# MCU.net
KiCad netlist of a schematic drawn in Altium Designer
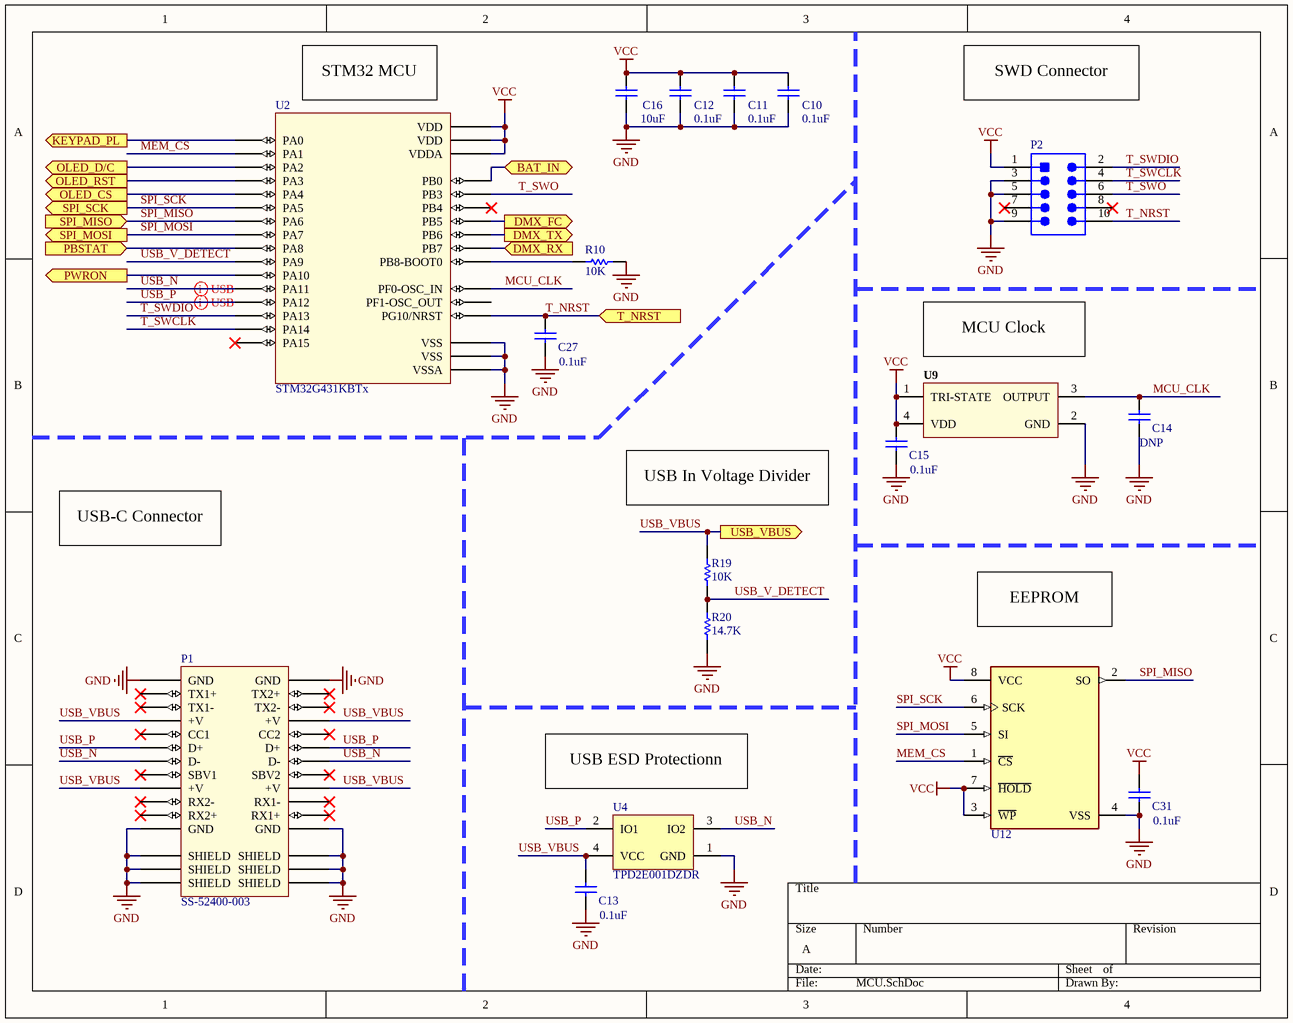
[diagram p0: MCU.SchDoc]

(export (version "E")
  (design (tool "Eeschema 10.0.6"))
  (components
    (comp (ref "C10")
      (value "0.1uF")
      (footprint "CAPC0603(1608)100_L")
      (description "CAP 27pF 16V ±0.5pF 0603 (1608 Metric) Thickness 1mm SMD")
      (fields (field (name "TOLERANCE") "Â±0.5pF"))
      (libsource (lib "Altium Content Vault") (part "CMP-1035-00873-1"))
    )
    (comp (ref "C11")
      (value "0.1uF")
      (footprint "CAPC0603(1608)100_L")
      (description "CAP 27pF 16V ±0.5pF 0603 (1608 Metric) Thickness 1mm SMD")
      (fields (field (name "TOLERANCE") "Â±0.5pF"))
      (libsource (lib "Altium Content Vault") (part "CMP-1035-00873-1"))
    )
    (comp (ref "C12")
      (value "0.1uF")
      (footprint "CAPC0603(1608)100_L")
      (description "CAP 27pF 16V ±0.5pF 0603 (1608 Metric) Thickness 1mm SMD")
      (fields (field (name "TOLERANCE") "Â±0.5pF"))
      (libsource (lib "Altium Content Vault") (part "CMP-1035-00873-1"))
    )
    (comp (ref "C13")
      (value "0.1uF")
      (footprint "CAPC0603(1608)100_L")
      (description "CAP 27pF 16V ±0.5pF 0603 (1608 Metric) Thickness 1mm SMD")
      (fields (field (name "TOLERANCE") "Â±0.5pF"))
      (libsource (lib "Altium Content Vault") (part "CMP-1035-00873-1"))
    )
    (comp (ref "C14")
      (value "DNP")
      (footprint "CAPC0603(1608)100_L")
      (description "CAP 27pF 16V ±0.5pF 0603 (1608 Metric) Thickness 1mm SMD")
      (fields (field (name "TOLERANCE") "Â±0.5pF"))
      (libsource (lib "Altium Content Vault") (part "CMP-1035-00873-1"))
    )
    (comp (ref "C15")
      (value "0.1uF")
      (footprint "CAPC0603(1608)100_L")
      (description "CAP 27pF 16V ±0.5pF 0603 (1608 Metric) Thickness 1mm SMD")
      (fields (field (name "TOLERANCE") "Â±0.5pF"))
      (libsource (lib "Altium Content Vault") (part "CMP-1035-00873-1"))
    )
    (comp (ref "C16")
      (value "10uF")
      (footprint "CAPC0603(1608)100_L")
      (description "CAP 27pF 16V ±0.5pF 0603 (1608 Metric) Thickness 1mm SMD")
      (fields (field (name "TOLERANCE") "Â±0.5pF"))
      (libsource (lib "Altium Content Vault") (part "CMP-1035-00873-1"))
    )
    (comp (ref "C27")
      (value "0.1uF")
      (footprint "CAPC0603(1608)100_L")
      (description "CAP 27pF 16V ±0.5pF 0603 (1608 Metric) Thickness 1mm SMD")
      (fields (field (name "TOLERANCE") "Â±0.5pF"))
      (libsource (lib "Altium Content Vault") (part "CMP-1035-00873-1"))
    )
    (comp (ref "C31")
      (value "0.1uF")
      (footprint "CAPC0603(1608)100_L")
      (description "CAP 27pF 16V ±0.5pF 0603 (1608 Metric) Thickness 1mm SMD")
      (fields (field (name "TOLERANCE") "Â±0.5pF"))
      (libsource (lib "Altium Content Vault") (part "CMP-1035-00873-1"))
    )
    (comp (ref "P1")
      (value "SS-52400-003")
      (footprint "SS-52400-00X")
      (libsource (lib "Belfuse") (part "SS-52400-003"))
    )
    (comp (ref "P2")
      (value "FTSH-105-01-F-DV-K")
      (footprint "SMTC-FTSH-105-01-L-DV-K_V")
      (description "Male Header, Pitch 1.27 mm, 2 x 5 Position, Height 6.12 mm, RoHS, Tube")
      (fields (field (name "MANUFACTURER") "Samtec"))
      (libsource (lib "Altium Content Vault") (part "CMP-2000-05352-1"))
    )
    (comp (ref "R10")
      (value "10K")
      (footprint "RESC0603(1608)_N")
      (description "Jumper 0603 (1608 Metric)")
      (fields (field (name "POWER") "None"))
      (libsource (lib "Altium Content Vault") (part "CMP-1012-00001-1"))
    )
    (comp (ref "R19")
      (value "10K")
      (footprint "RESC0603(1608)_N")
      (description "Jumper 0603 (1608 Metric)")
      (fields (field (name "POWER") "None"))
      (libsource (lib "Altium Content Vault") (part "CMP-1012-00001-1"))
    )
    (comp (ref "R20")
      (value "14.7K")
      (footprint "RESC0603(1608)_N")
      (description "Jumper 0603 (1608 Metric)")
      (fields (field (name "POWER") "None"))
      (libsource (lib "Altium Content Vault") (part "CMP-1012-00001-1"))
    )
    (comp (ref "U2")
      (value "STM32G431KBTx")
      (footprint "LQFP32")
      (libsource (lib "STMicroelectronics") (part "STM32G431KBTx"))
    )
    (comp (ref "U4")
      (value "TPD2E001DZDR")
      (footprint "DZD0004A_N")
      (fields (field (name "MANUFACTURER") "Texas Instruments"))
      (libsource (lib "Altium Content Vault") (part "TI-TPD2E001-SOP_DZD-4"))
    )
    (comp (ref "U9")
      (value "XLH536024.000000I")
      (footprint "ECS-396X_V")
      (description "Clock Oscillator, 3.3 V, 25 MHz, -55 to 125 degC, 4-Pin SMD, RoHS, Tape and Reel")
      (fields (field (name "MANUFACTURER") "ECS"))
      (libsource (lib "Altium Content Vault") (part "CMP-2000-06192-1"))
    )
    (comp (ref "U12")
      (value "CAT25640VI-GT3")
      (footprint "FP-CAT25256VI-GT3-IPC_B")
      (description "IC EEPROM 256K SPI 20MHZ 8SOIC")
      (fields
        (field (name "MANUFACTURER") "ON Semiconductor")
        (field (name "MANUFACTURER PART NUMBER") "CAT25256VI-GT3")
      )
      (libsource (lib "Altium Content Vault") (part "CMP-07117-000003-1"))
    )
  )
  (nets
    (net (code "1") (name "/BAT_IN") (class "Default")
      (node (ref "U2") (pin "13") (pinfunction "PB0_13") (pintype "bidirectional"))
    )
    (net (code "2") (name "/DMX_FC") (class "Default")
      (node (ref "U2") (pin "28") (pinfunction "PB5_28") (pintype "bidirectional"))
    )
    (net (code "3") (name "/DMX_RX") (class "Default")
      (node (ref "U2") (pin "30") (pinfunction "PB7_30") (pintype "bidirectional"))
    )
    (net (code "4") (name "/DMX_TX") (class "Default")
      (node (ref "U2") (pin "29") (pinfunction "PB6_29") (pintype "bidirectional"))
    )
    (net (code "5") (name "/KEYPAD_PL") (class "Default")
      (node (ref "U2") (pin "5") (pinfunction "PA0_5") (pintype "bidirectional"))
    )
    (net (code "6") (name "/MCU_CLK") (class "Default")
      (node (ref "C14") (pin "2") (pinfunction "2_2") (pintype "passive"))
      (node (ref "U2") (pin "2") (pinfunction "PF0-OSC_IN_2") (pintype "bidirectional"))
      (node (ref "U9") (pin "3") (pinfunction "OUTPUT_3") (pintype "passive"))
    )
    (net (code "7") (name "/MEM_CS") (class "Default")
      (node (ref "U12") (pin "1") (pinfunction "~{CS}_1") (pintype "input"))
      (node (ref "U2") (pin "6") (pinfunction "PA1_6") (pintype "bidirectional"))
    )
    (net (code "8") (name "/OLED_CS") (class "Default")
      (node (ref "U2") (pin "9") (pinfunction "PA4_9") (pintype "bidirectional"))
    )
    (net (code "9") (name "/OLED_D{slash}C") (class "Default")
      (node (ref "U2") (pin "7") (pinfunction "PA2_7") (pintype "bidirectional"))
    )
    (net (code "10") (name "/OLED_RST") (class "Default")
      (node (ref "U2") (pin "8") (pinfunction "PA3_8") (pintype "bidirectional"))
    )
    (net (code "11") (name "/PBSTAT") (class "Default")
      (node (ref "U2") (pin "18") (pinfunction "PA8_18") (pintype "bidirectional"))
    )
    (net (code "12") (name "/PWRON") (class "Default")
      (node (ref "U2") (pin "20") (pinfunction "PA10_20") (pintype "bidirectional"))
    )
    (net (code "13") (name "/SPI_MISO") (class "Default")
      (node (ref "U12") (pin "2") (pinfunction "SO_2") (pintype "output"))
      (node (ref "U2") (pin "11") (pinfunction "PA6_11") (pintype "bidirectional"))
    )
    (net (code "14") (name "/SPI_MOSI") (class "Default")
      (node (ref "U12") (pin "5") (pinfunction "SI_5") (pintype "input"))
      (node (ref "U2") (pin "12") (pinfunction "PA7_12") (pintype "bidirectional"))
    )
    (net (code "15") (name "/SPI_SCK") (class "Default")
      (node (ref "U12") (pin "6") (pinfunction "SCK_6") (pintype "input"))
      (node (ref "U2") (pin "10") (pinfunction "PA5_10") (pintype "bidirectional"))
    )
    (net (code "16") (name "/T_NRST") (class "Default")
      (node (ref "C27") (pin "2") (pinfunction "2_2") (pintype "passive"))
      (node (ref "P2") (pin "10") (pinfunction "10_10") (pintype "passive"))
      (node (ref "U2") (pin "4") (pinfunction "PG10/NRST_4") (pintype "bidirectional"))
    )
    (net (code "17") (name "/T_SWCLK") (class "Default")
      (node (ref "P2") (pin "4") (pinfunction "4_4") (pintype "passive"))
      (node (ref "U2") (pin "24") (pinfunction "PA14_24") (pintype "bidirectional"))
    )
    (net (code "18") (name "/T_SWDIO") (class "Default")
      (node (ref "P2") (pin "2") (pinfunction "2_2") (pintype "passive"))
      (node (ref "U2") (pin "23") (pinfunction "PA13_23") (pintype "bidirectional"))
    )
    (net (code "19") (name "/T_SWO") (class "Default")
      (node (ref "P2") (pin "6") (pinfunction "6_6") (pintype "passive"))
      (node (ref "U2") (pin "26") (pinfunction "PB3_26") (pintype "bidirectional"))
    )
    (net (code "20") (name "/USB_N") (class "Default")
      (node (ref "P1") (pin "A7") (pinfunction "D-_A7") (pintype "bidirectional"))
      (node (ref "P1") (pin "B7") (pinfunction "D-_B7") (pintype "bidirectional"))
      (node (ref "U2") (pin "21") (pinfunction "PA11_21") (pintype "bidirectional"))
      (node (ref "U4") (pin "3") (pinfunction "IO2_3") (pintype "passive"))
    )
    (net (code "21") (name "/USB_P") (class "Default")
      (node (ref "P1") (pin "A6") (pinfunction "D+_A6") (pintype "bidirectional"))
      (node (ref "P1") (pin "B6") (pinfunction "D+_B6") (pintype "bidirectional"))
      (node (ref "U2") (pin "22") (pinfunction "PA12_22") (pintype "bidirectional"))
      (node (ref "U4") (pin "2") (pinfunction "IO1_2") (pintype "passive"))
    )
    (net (code "22") (name "/USB_VBUS") (class "Default")
      (node (ref "C13") (pin "2") (pinfunction "2_2") (pintype "passive"))
      (node (ref "P1") (pin "A4") (pinfunction "+V_A4") (pintype "power_in"))
      (node (ref "P1") (pin "A9") (pinfunction "+V_A9") (pintype "power_in"))
      (node (ref "P1") (pin "B4") (pinfunction "+V_B4") (pintype "power_in"))
      (node (ref "P1") (pin "B9") (pinfunction "+V_B9") (pintype "power_in"))
      (node (ref "R19") (pin "1") (pinfunction "1_1") (pintype "passive"))
      (node (ref "U4") (pin "4") (pinfunction "VCC_4") (pintype "power_in"))
    )
    (net (code "23") (name "/USB_V_DETECT") (class "Default")
      (node (ref "R19") (pin "2") (pinfunction "2_2") (pintype "passive"))
      (node (ref "R20") (pin "2") (pinfunction "2_2") (pintype "passive"))
      (node (ref "U2") (pin "19") (pinfunction "PA9_19") (pintype "bidirectional"))
    )
    (net (code "24") (name "GND") (class "Default")
      (node (ref "C10") (pin "1") (pinfunction "1_1") (pintype "passive"))
      (node (ref "C11") (pin "1") (pinfunction "1_1") (pintype "passive"))
      (node (ref "C12") (pin "1") (pinfunction "1_1") (pintype "passive"))
      (node (ref "C13") (pin "1") (pinfunction "1_1") (pintype "passive"))
      (node (ref "C14") (pin "1") (pinfunction "1_1") (pintype "passive"))
      (node (ref "C15") (pin "1") (pinfunction "1_1") (pintype "passive"))
      (node (ref "C16") (pin "1") (pinfunction "1_1") (pintype "passive"))
      (node (ref "C27") (pin "1") (pinfunction "1_1") (pintype "passive"))
      (node (ref "C31") (pin "1") (pinfunction "1_1") (pintype "passive"))
      (node (ref "P1") (pin "A1") (pinfunction "GND_A1") (pintype "power_in"))
      (node (ref "P1") (pin "A12") (pinfunction "GND_A12") (pintype "power_in"))
      (node (ref "P1") (pin "B1") (pinfunction "GND_B1") (pintype "power_in"))
      (node (ref "P1") (pin "B12") (pinfunction "GND_B12") (pintype "power_in"))
      (node (ref "P1") (pin "G1") (pinfunction "SHIELD_G1") (pintype "power_in"))
      (node (ref "P1") (pin "G2") (pinfunction "SHIELD_G2") (pintype "power_in"))
      (node (ref "P1") (pin "G3") (pinfunction "SHIELD_G3") (pintype "power_in"))
      (node (ref "P1") (pin "G4") (pinfunction "SHIELD_G4") (pintype "power_in"))
      (node (ref "P1") (pin "G5") (pinfunction "SHIELD_G5") (pintype "power_in"))
      (node (ref "P1") (pin "G6") (pinfunction "SHIELD_G6") (pintype "power_in"))
      (node (ref "P2") (pin "3") (pinfunction "3_3") (pintype "passive"))
      (node (ref "P2") (pin "5") (pinfunction "5_5") (pintype "passive"))
      (node (ref "P2") (pin "9") (pinfunction "9_9") (pintype "passive"))
      (node (ref "R10") (pin "2") (pinfunction "2_2") (pintype "passive"))
      (node (ref "R20") (pin "1") (pinfunction "1_1") (pintype "passive"))
      (node (ref "U12") (pin "4") (pinfunction "VSS_4") (pintype "power_in"))
      (node (ref "U2") (pin "14") (pinfunction "VSSA_14") (pintype "power_in"))
      (node (ref "U2") (pin "16") (pinfunction "VSS_16") (pintype "power_in"))
      (node (ref "U2") (pin "32") (pinfunction "VSS_32") (pintype "power_in"))
      (node (ref "U4") (pin "1") (pinfunction "GND_1") (pintype "power_in"))
      (node (ref "U9") (pin "2") (pinfunction "GND_2") (pintype "power_in"))
    )
    (net (code "25") (name "Net-(U2-PB8-BOOT0)") (class "Default")
      (node (ref "R10") (pin "1") (pinfunction "1_1") (pintype "passive"))
      (node (ref "U2") (pin "31") (pinfunction "PB8-BOOT0_31") (pintype "bidirectional"))
    )
    (net (code "26") (name "VCC") (class "Default")
      (node (ref "C10") (pin "2") (pinfunction "2_2") (pintype "passive"))
      (node (ref "C11") (pin "2") (pinfunction "2_2") (pintype "passive"))
      (node (ref "C12") (pin "2") (pinfunction "2_2") (pintype "passive"))
      (node (ref "C15") (pin "2") (pinfunction "2_2") (pintype "passive"))
      (node (ref "C16") (pin "2") (pinfunction "2_2") (pintype "passive"))
      (node (ref "C31") (pin "2") (pinfunction "2_2") (pintype "passive"))
      (node (ref "P2") (pin "1") (pinfunction "1_1") (pintype "passive"))
      (node (ref "U12") (pin "3") (pinfunction "~{WP}_3") (pintype "input"))
      (node (ref "U12") (pin "7") (pinfunction "~{HOLD}_7") (pintype "input"))
      (node (ref "U12") (pin "8") (pinfunction "VCC_8") (pintype "power_in"))
      (node (ref "U2") (pin "1") (pinfunction "VDD_1") (pintype "power_in"))
      (node (ref "U2") (pin "15") (pinfunction "VDDA_15") (pintype "power_in"))
      (node (ref "U2") (pin "17") (pinfunction "VDD_17") (pintype "power_in"))
      (node (ref "U9") (pin "1") (pinfunction "TRI-STATE_1") (pintype "passive"))
      (node (ref "U9") (pin "4") (pinfunction "VDD_4") (pintype "power_in"))
    )
    (net (code "27") (name "unconnected-(P1-CC1-PadA5)") (class "Default")
      (node (ref "P1") (pin "A5") (pinfunction "CC1_A5") (pintype "bidirectional+no_connect"))
    )
    (net (code "28") (name "unconnected-(P1-CC2-PadB5)") (class "Default")
      (node (ref "P1") (pin "B5") (pinfunction "CC2_B5") (pintype "bidirectional+no_connect"))
    )
    (net (code "29") (name "unconnected-(P1-RX1+-PadB11)") (class "Default")
      (node (ref "P1") (pin "B11") (pinfunction "RX1+_B11") (pintype "bidirectional+no_connect"))
    )
    (net (code "30") (name "unconnected-(P1-RX1--PadB10)") (class "Default")
      (node (ref "P1") (pin "B10") (pinfunction "RX1-_B10") (pintype "power_in+no_connect"))
    )
    (net (code "31") (name "unconnected-(P1-RX2+-PadA11)") (class "Default")
      (node (ref "P1") (pin "A11") (pinfunction "RX2+_A11") (pintype "bidirectional+no_connect"))
    )
    (net (code "32") (name "unconnected-(P1-RX2--PadA10)") (class "Default")
      (node (ref "P1") (pin "A10") (pinfunction "RX2-_A10") (pintype "bidirectional+no_connect"))
    )
    (net (code "33") (name "unconnected-(P1-SBV1-PadA8)") (class "Default")
      (node (ref "P1") (pin "A8") (pinfunction "SBV1_A8") (pintype "bidirectional+no_connect"))
    )
    (net (code "34") (name "unconnected-(P1-SBV2-PadB8)") (class "Default")
      (node (ref "P1") (pin "B8") (pinfunction "SBV2_B8") (pintype "bidirectional+no_connect"))
    )
    (net (code "35") (name "unconnected-(P1-TX1+-PadA2)") (class "Default")
      (node (ref "P1") (pin "A2") (pinfunction "TX1+_A2") (pintype "bidirectional+no_connect"))
    )
    (net (code "36") (name "unconnected-(P1-TX1--PadA3)") (class "Default")
      (node (ref "P1") (pin "A3") (pinfunction "TX1-_A3") (pintype "bidirectional+no_connect"))
    )
    (net (code "37") (name "unconnected-(P1-TX2+-PadB2)") (class "Default")
      (node (ref "P1") (pin "B2") (pinfunction "TX2+_B2") (pintype "bidirectional+no_connect"))
    )
    (net (code "38") (name "unconnected-(P1-TX2--PadB3)") (class "Default")
      (node (ref "P1") (pin "B3") (pinfunction "TX2-_B3") (pintype "bidirectional+no_connect"))
    )
    (net (code "39") (name "unconnected-(P2-Pad7)") (class "Default")
      (node (ref "P2") (pin "7") (pinfunction "7_7") (pintype "passive+no_connect"))
    )
    (net (code "40") (name "unconnected-(P2-Pad8)") (class "Default")
      (node (ref "P2") (pin "8") (pinfunction "8_8") (pintype "passive+no_connect"))
    )
    (net (code "41") (name "unconnected-(U2-PA15-Pad25)") (class "Default")
      (node (ref "U2") (pin "25") (pinfunction "PA15_25") (pintype "bidirectional+no_connect"))
    )
    (net (code "42") (name "unconnected-(U2-PB4-Pad27)") (class "Default")
      (node (ref "U2") (pin "27") (pinfunction "PB4_27") (pintype "bidirectional+no_connect"))
    )
    (net (code "43") (name "unconnected-(U2-PF1-OSC_OUT-Pad3)") (class "Default")
      (node (ref "U2") (pin "3") (pinfunction "PF1-OSC_OUT_3") (pintype "bidirectional"))
    )
  )
)
